# Fiber_interlock.net
KiCad netlist of a schematic drawn in Altium Designer
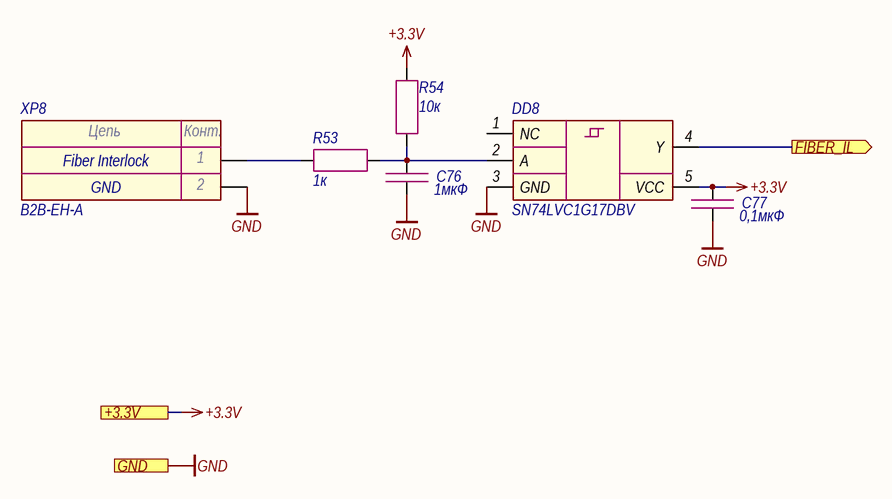
[diagram p0: Fiber_interlock.SchDoc]

(export (version "E")
  (design (tool "Eeschema 10.0.6"))
  (components
    (comp (ref "C76")
      (value "1мкФ")
      (footprint "Pcb_library:CAP_0603")
      (fields (field (name "MANUFACTURER") "Murata"))
      (libsource (lib "Schem_library") (part "Capacitor"))
    )
    (comp (ref "C77")
      (value "0,1мкФ")
      (footprint "Pcb_library:CAP_0603")
      (fields (field (name "MANUFACTURER") "Murata"))
      (libsource (lib "Schem_library") (part "Capacitor"))
    )
    (comp (ref "DD8")
      (value "SN74LVC1G17DBV")
      (footprint "Pcb_library:SOT-23-5")
      (fields (field (name "MANUFACTURER") "Texas Instruments"))
      (libsource (lib "Schem_library") (part "SN74LVC1G17"))
    )
    (comp (ref "R53")
      (value "1к")
      (footprint "Pcb_library:RES_0603")
      (fields (field (name "MANUFACTURER") "Yageo"))
      (libsource (lib "Schem_library") (part "Resistor"))
    )
    (comp (ref "R54")
      (value "10к")
      (footprint "Pcb_library:RES_0603")
      (fields (field (name "MANUFACTURER") "Yageo"))
      (libsource (lib "Schem_library") (part "Resistor"))
    )
    (comp (ref "XP8")
      (value "B2B-EH-A")
      (footprint "Pcb_library:B2B-EH-A")
      (fields (field (name "MANUFACTURER") "JST"))
      (libsource (lib "Schem_library") (part "Connector-2"))
    )
  )
  (nets
    (net (code "1") (name "+3.3V") (class "Default")
      (node (ref "C77") (pin "1") (pinfunction "1_1") (pintype "passive"))
      (node (ref "DD8") (pin "5") (pinfunction "VCC_5") (pintype "passive"))
      (node (ref "R54") (pin "2") (pinfunction "2_2") (pintype "passive"))
    )
    (net (code "2") (name "/FIBER_IL") (class "Default")
      (node (ref "DD8") (pin "4") (pinfunction "Y_4") (pintype "passive"))
    )
    (net (code "3") (name "GND") (class "Default")
      (node (ref "C76") (pin "2") (pinfunction "2_2") (pintype "passive"))
      (node (ref "C77") (pin "2") (pinfunction "2_2") (pintype "passive"))
      (node (ref "DD8") (pin "3") (pinfunction "GND_3") (pintype "passive"))
      (node (ref "XP8") (pin "2") (pintype "passive"))
    )
    (net (code "4") (name "Net-(DD8-A)") (class "Default")
      (node (ref "C76") (pin "1") (pinfunction "1_1") (pintype "passive"))
      (node (ref "DD8") (pin "2") (pinfunction "A_2") (pintype "passive"))
      (node (ref "R53") (pin "2") (pinfunction "2_2") (pintype "passive"))
      (node (ref "R54") (pin "1") (pinfunction "1_1") (pintype "passive"))
    )
    (net (code "5") (name "Net-(R53-Pad1)") (class "Default")
      (node (ref "R53") (pin "1") (pinfunction "1_1") (pintype "passive"))
      (node (ref "XP8") (pin "1") (pintype "passive"))
    )
    (net (code "6") (name "unconnected-(DD8-NC-Pad1)") (class "Default")
      (node (ref "DD8") (pin "1") (pinfunction "NC_1") (pintype "passive"))
    )
  )
)
